# G826X.net
KiCad netlist of a schematic drawn in EAGLE
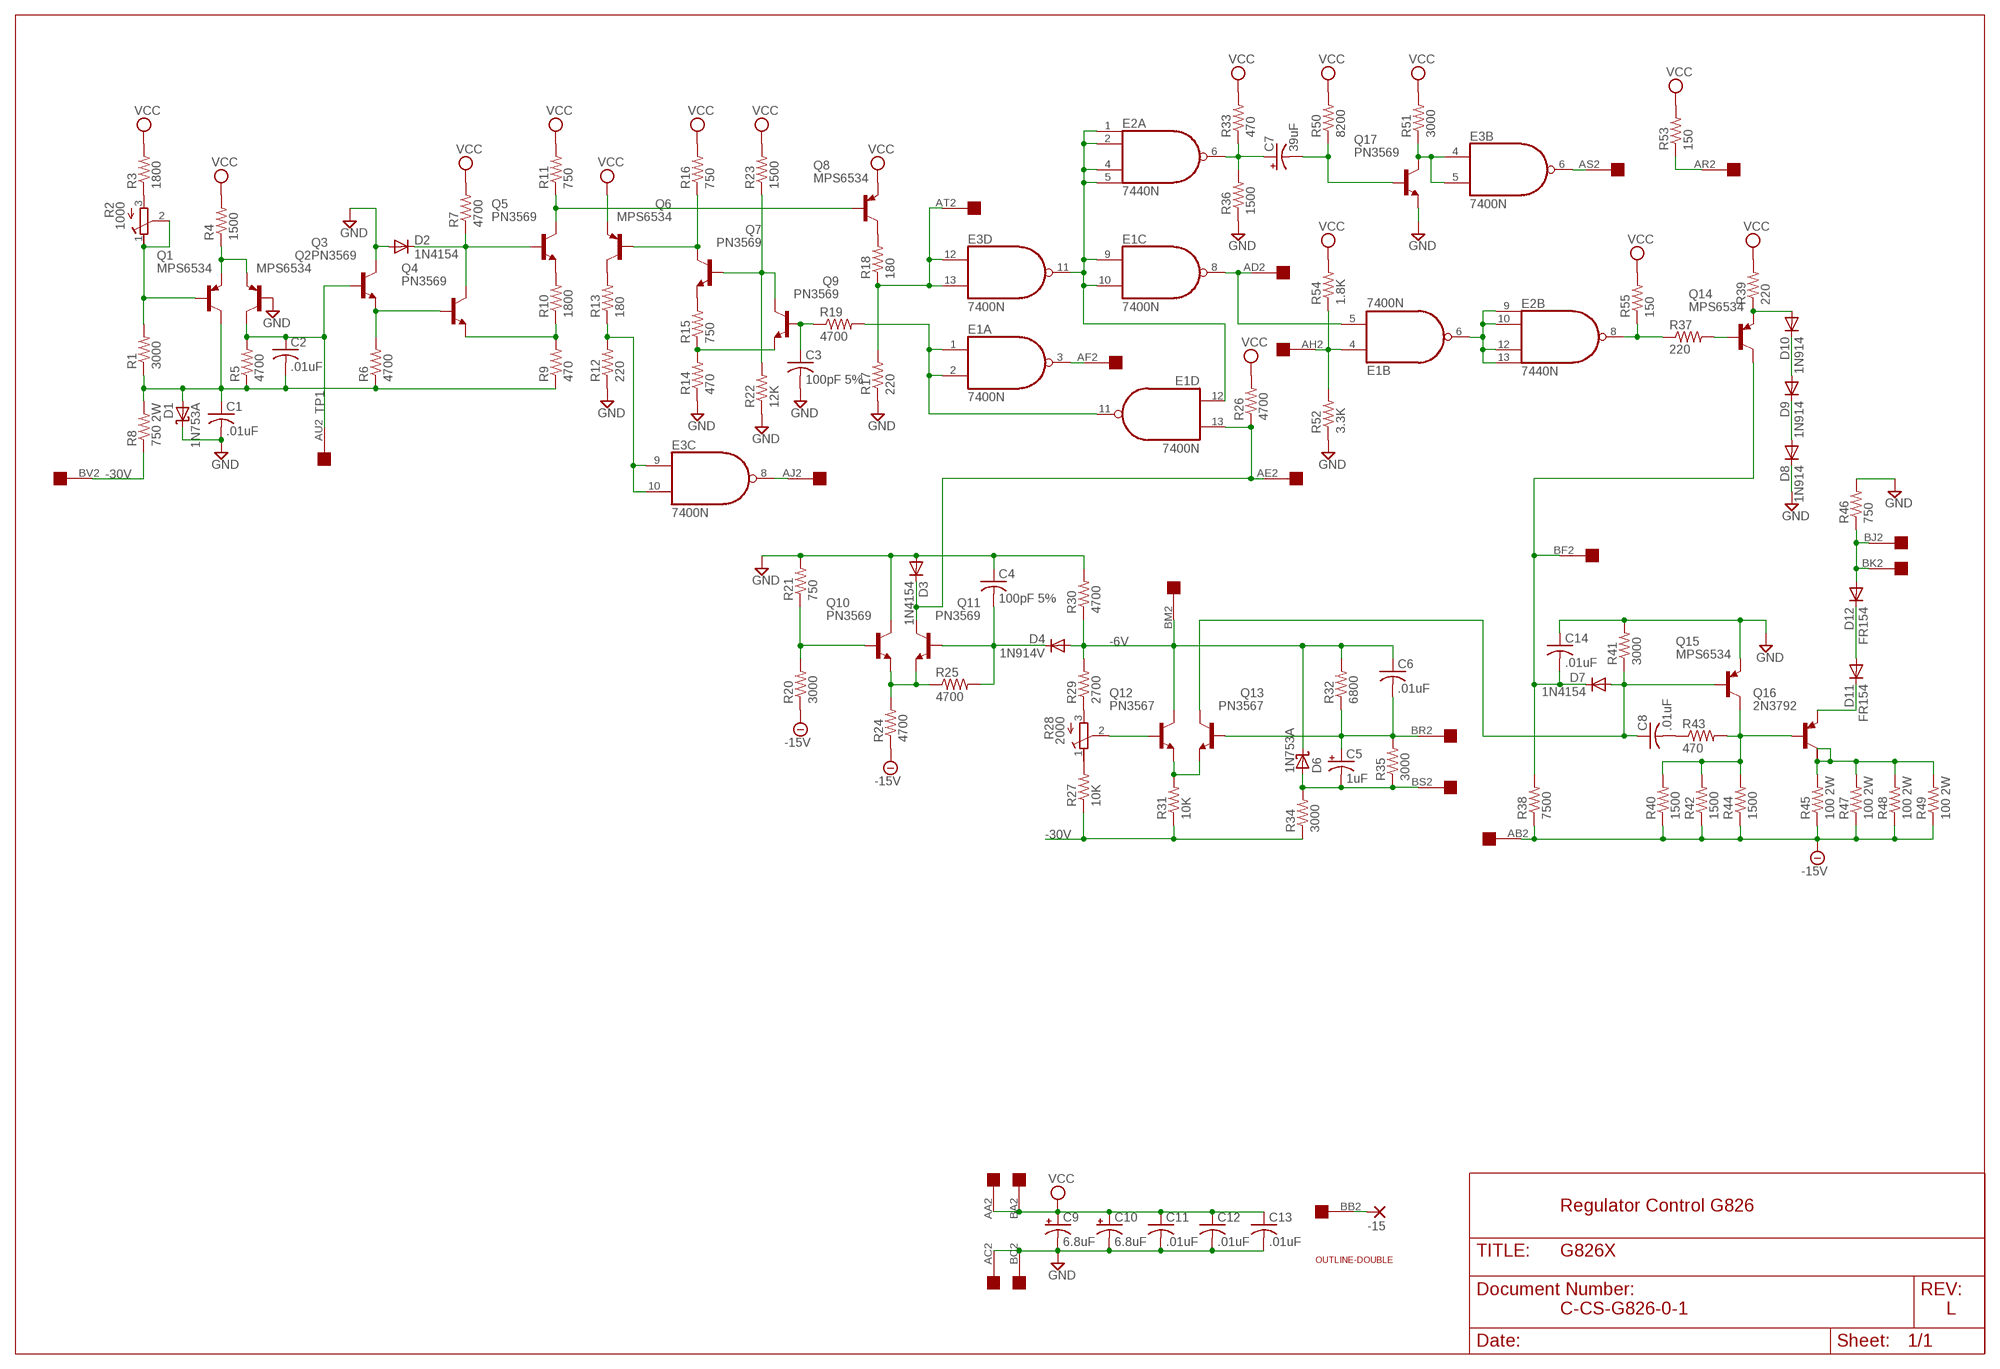
[diagram p0: schematic, sheet 1]

(export (version "E")
  (design (tool "Eeschema 10.0.6"))
  (components
    (comp (ref "-15")
      (value "1,6/0,8")
      (footprint "eagle-import:1,6_0,8")
      (libsource (lib "eagle-import") (part "1,6/0,8"))
    )
    (comp (ref "C1")
      (value ".01uF")
      (footprint "eagle-import:C050-025X075")
      (libsource (lib "eagle-import") (part "C-US050-025X075"))
    )
    (comp (ref "C2")
      (value ".01uF")
      (footprint "eagle-import:C050-025X075")
      (libsource (lib "eagle-import") (part "C-US050-025X075"))
    )
    (comp (ref "C3")
      (value "100pF 5%")
      (footprint "eagle-import:C050-025X075")
      (libsource (lib "eagle-import") (part "C-US050-025X075"))
    )
    (comp (ref "C4")
      (value "100pF 5%")
      (footprint "eagle-import:C050-025X075")
      (libsource (lib "eagle-import") (part "C-US050-025X075"))
    )
    (comp (ref "C5")
      (value "1uF")
      (footprint "eagle-import:E15-5")
      (libsource (lib "eagle-import") (part "CPOL-USE15-5AXIAL"))
    )
    (comp (ref "C6")
      (value ".01uF")
      (footprint "eagle-import:C050-025X075")
      (libsource (lib "eagle-import") (part "C-US050-025X075"))
    )
    (comp (ref "C7")
      (value "39uF")
      (footprint "eagle-import:E22-6")
      (libsource (lib "eagle-import") (part "CPOL-USE22-6AXIAL"))
    )
    (comp (ref "C8")
      (value ".01uF")
      (footprint "eagle-import:C050-025X075")
      (libsource (lib "eagle-import") (part "C-US050-025X075"))
    )
    (comp (ref "C9")
      (value "6.8uF")
      (footprint "eagle-import:E12-8")
      (libsource (lib "eagle-import") (part "CPOL-USE20-8AXIAL"))
    )
    (comp (ref "C10")
      (value "6.8uF")
      (footprint "eagle-import:E12-8")
      (libsource (lib "eagle-import") (part "CPOL-USE20-8AXIAL"))
    )
    (comp (ref "C11")
      (value ".01uF")
      (footprint "eagle-import:C050-025X075")
      (libsource (lib "eagle-import") (part "C-US050-025X075"))
    )
    (comp (ref "C12")
      (value ".01uF")
      (footprint "eagle-import:C050-025X075")
      (libsource (lib "eagle-import") (part "C-US050-025X075"))
    )
    (comp (ref "C13")
      (value ".01uF")
      (footprint "eagle-import:C050-025X075")
      (libsource (lib "eagle-import") (part "C-US050-025X075"))
    )
    (comp (ref "C14")
      (value ".01uF")
      (footprint "eagle-import:C050-025X075")
      (libsource (lib "eagle-import") (part "C-US050-025X075"))
    )
    (comp (ref "D1")
      (value "1N753A")
      (footprint "eagle-import:DO35-10")
      (libsource (lib "eagle-import") (part "BAT42"))
    )
    (comp (ref "D2")
      (value "1N4154")
      (footprint "eagle-import:DO35-10")
      (libsource (lib "eagle-import") (part "1N4148"))
    )
    (comp (ref "D3")
      (value "1N4154")
      (footprint "eagle-import:DO35-10")
      (libsource (lib "eagle-import") (part "1N4148"))
    )
    (comp (ref "D4")
      (value "1N914V")
      (footprint "eagle-import:DO35-10")
      (libsource (lib "eagle-import") (part "1N4148"))
    )
    (comp (ref "D6")
      (value "1N753A")
      (footprint "eagle-import:DO35-10")
      (libsource (lib "eagle-import") (part "BAT42"))
    )
    (comp (ref "D7")
      (value "1N4154")
      (footprint "eagle-import:DO35-10")
      (libsource (lib "eagle-import") (part "1N4148"))
    )
    (comp (ref "D8")
      (value "1N914")
      (footprint "eagle-import:DO35-10")
      (libsource (lib "eagle-import") (part "1N4148"))
    )
    (comp (ref "D9")
      (value "1N914")
      (footprint "eagle-import:DO35-10")
      (libsource (lib "eagle-import") (part "1N4148"))
    )
    (comp (ref "D10")
      (value "1N914")
      (footprint "eagle-import:DO35-10")
      (libsource (lib "eagle-import") (part "1N4148"))
    )
    (comp (ref "D11")
      (value "FR154")
      (footprint "eagle-import:DO41-10")
      (libsource (lib "eagle-import") (part "1N4004"))
    )
    (comp (ref "D12")
      (value "FR154")
      (footprint "eagle-import:DO41-10")
      (libsource (lib "eagle-import") (part "1N4004"))
    )
    (comp (ref "E1")
      (value "7400N")
      (footprint "eagle-import:DIL14")
      (libsource (lib "eagle-import") (part "7400N"))
    )
    (comp (ref "E2")
      (value "7440N")
      (footprint "eagle-import:DIL14")
      (libsource (lib "eagle-import") (part "7420NS"))
    )
    (comp (ref "E3")
      (value "7400N")
      (footprint "eagle-import:DIL14")
      (libsource (lib "eagle-import") (part "7400N"))
    )
    (comp (ref "Q1")
      (value "MPS6534")
      (footprint "eagle-import:TO39")
      (libsource (lib "eagle-import") (part "2N2904"))
    )
    (comp (ref "Q2")
      (value "MPS6534")
      (footprint "eagle-import:TO39")
      (libsource (lib "eagle-import") (part "2N2904"))
    )
    (comp (ref "Q3")
      (value "PN3569")
      (footprint "eagle-import:TO5")
      (libsource (lib "eagle-import") (part "2N2219"))
    )
    (comp (ref "Q4")
      (value "PN3569")
      (footprint "eagle-import:TO5")
      (libsource (lib "eagle-import") (part "2N2219"))
    )
    (comp (ref "Q5")
      (value "PN3569")
      (footprint "eagle-import:TO5")
      (libsource (lib "eagle-import") (part "2N2219"))
    )
    (comp (ref "Q6")
      (value "MPS6534")
      (footprint "eagle-import:TO39")
      (libsource (lib "eagle-import") (part "2N2904"))
    )
    (comp (ref "Q7")
      (value "PN3569")
      (footprint "eagle-import:TO5")
      (libsource (lib "eagle-import") (part "2N2219"))
    )
    (comp (ref "Q8")
      (value "MPS6534")
      (footprint "eagle-import:TO39")
      (libsource (lib "eagle-import") (part "2N2904"))
    )
    (comp (ref "Q9")
      (value "PN3569")
      (footprint "eagle-import:TO5")
      (libsource (lib "eagle-import") (part "2N2219"))
    )
    (comp (ref "Q10")
      (value "PN3569")
      (footprint "eagle-import:TO5")
      (libsource (lib "eagle-import") (part "2N2219"))
    )
    (comp (ref "Q11")
      (value "PN3569")
      (footprint "eagle-import:TO5")
      (libsource (lib "eagle-import") (part "2N2219"))
    )
    (comp (ref "Q12")
      (value "PN3567")
      (footprint "eagle-import:TO5")
      (libsource (lib "eagle-import") (part "2N2219"))
    )
    (comp (ref "Q13")
      (value "PN3567")
      (footprint "eagle-import:TO5")
      (libsource (lib "eagle-import") (part "2N2219"))
    )
    (comp (ref "Q14")
      (value "MPS6534")
      (footprint "eagle-import:TO39")
      (libsource (lib "eagle-import") (part "2N2904"))
    )
    (comp (ref "Q15")
      (value "MPS6534")
      (footprint "eagle-import:TO39")
      (libsource (lib "eagle-import") (part "2N2904"))
    )
    (comp (ref "Q16")
      (value "2N3792")
      (footprint "eagle-import:TO3")
      (libsource (lib "eagle-import") (part "2N4902"))
    )
    (comp (ref "Q17")
      (value "PN3569")
      (footprint "eagle-import:TO5")
      (libsource (lib "eagle-import") (part "2N2219"))
    )
    (comp (ref "R1")
      (value "3000")
      (footprint "eagle-import:0207_10")
      (libsource (lib "eagle-import") (part "R-US_0207/10"))
    )
    (comp (ref "R2")
      (value "1000")
      (footprint "eagle-import:3006Y")
      (libsource (lib "eagle-import") (part "275P"))
    )
    (comp (ref "R3")
      (value "1800")
      (footprint "eagle-import:0207_10")
      (libsource (lib "eagle-import") (part "R-US_0207/10"))
    )
    (comp (ref "R4")
      (value "1500")
      (footprint "eagle-import:0207_10")
      (libsource (lib "eagle-import") (part "R-US_0207/10"))
    )
    (comp (ref "R5")
      (value "4700")
      (footprint "eagle-import:0207_10")
      (libsource (lib "eagle-import") (part "R-US_0207/10"))
    )
    (comp (ref "R6")
      (value "4700")
      (footprint "eagle-import:0207_10")
      (libsource (lib "eagle-import") (part "R-US_0207/10"))
    )
    (comp (ref "R7")
      (value "4700")
      (footprint "eagle-import:0207_10")
      (libsource (lib "eagle-import") (part "R-US_0207/10"))
    )
    (comp (ref "R8")
      (value "750 2W")
      (footprint "eagle-import:0818_25")
      (libsource (lib "eagle-import") (part "R-US_0818/25"))
    )
    (comp (ref "R9")
      (value "470")
      (footprint "eagle-import:0207_10")
      (libsource (lib "eagle-import") (part "R-US_0207/10"))
    )
    (comp (ref "R10")
      (value "1800")
      (footprint "eagle-import:0207_10")
      (libsource (lib "eagle-import") (part "R-US_0207/10"))
    )
    (comp (ref "R11")
      (value "750")
      (footprint "eagle-import:0207_10")
      (libsource (lib "eagle-import") (part "R-US_0207/10"))
    )
    (comp (ref "R12")
      (value "220")
      (footprint "eagle-import:0207_10")
      (libsource (lib "eagle-import") (part "R-US_0207/10"))
    )
    (comp (ref "R13")
      (value "180")
      (footprint "eagle-import:0207_10")
      (libsource (lib "eagle-import") (part "R-US_0207/10"))
    )
    (comp (ref "R14")
      (value "470")
      (footprint "eagle-import:0207_10")
      (libsource (lib "eagle-import") (part "R-US_0207/10"))
    )
    (comp (ref "R15")
      (value "750")
      (footprint "eagle-import:0207_10")
      (libsource (lib "eagle-import") (part "R-US_0207/10"))
    )
    (comp (ref "R16")
      (value "750")
      (footprint "eagle-import:0207_10")
      (libsource (lib "eagle-import") (part "R-US_0207/10"))
    )
    (comp (ref "R17")
      (value "220")
      (footprint "eagle-import:0207_10")
      (libsource (lib "eagle-import") (part "R-US_0207/10"))
    )
    (comp (ref "R18")
      (value "180")
      (footprint "eagle-import:0207_10")
      (libsource (lib "eagle-import") (part "R-US_0207/10"))
    )
    (comp (ref "R19")
      (value "4700")
      (footprint "eagle-import:0207_10")
      (libsource (lib "eagle-import") (part "R-US_0207/10"))
    )
    (comp (ref "R20")
      (value "3000")
      (footprint "eagle-import:0207_10")
      (libsource (lib "eagle-import") (part "R-US_0207/10"))
    )
    (comp (ref "R21")
      (value "750")
      (footprint "eagle-import:0207_10")
      (libsource (lib "eagle-import") (part "R-US_0207/10"))
    )
    (comp (ref "R22")
      (value "12K")
      (footprint "eagle-import:0207_10")
      (libsource (lib "eagle-import") (part "R-US_0207/10"))
    )
    (comp (ref "R23")
      (value "1500")
      (footprint "eagle-import:0207_10")
      (libsource (lib "eagle-import") (part "R-US_0207/10"))
    )
    (comp (ref "R24")
      (value "4700")
      (footprint "eagle-import:0207_10")
      (libsource (lib "eagle-import") (part "R-US_0207/10"))
    )
    (comp (ref "R25")
      (value "4700")
      (footprint "eagle-import:0207_10")
      (libsource (lib "eagle-import") (part "R-US_0207/10"))
    )
    (comp (ref "R26")
      (value "4700")
      (footprint "eagle-import:0207_10")
      (libsource (lib "eagle-import") (part "R-US_0207/10"))
    )
    (comp (ref "R27")
      (value "10K")
      (footprint "eagle-import:0207_10")
      (libsource (lib "eagle-import") (part "R-US_0207/10"))
    )
    (comp (ref "R28")
      (value "2000")
      (footprint "eagle-import:3006Y")
      (libsource (lib "eagle-import") (part "275P"))
    )
    (comp (ref "R29")
      (value "2700")
      (footprint "eagle-import:0207_10")
      (libsource (lib "eagle-import") (part "R-US_0207/10"))
    )
    (comp (ref "R30")
      (value "4700")
      (footprint "eagle-import:0207_10")
      (libsource (lib "eagle-import") (part "R-US_0207/10"))
    )
    (comp (ref "R31")
      (value "10K")
      (footprint "eagle-import:0207_10")
      (libsource (lib "eagle-import") (part "R-US_0207/10"))
    )
    (comp (ref "R32")
      (value "6800")
      (footprint "eagle-import:0207_10")
      (libsource (lib "eagle-import") (part "R-US_0207/10"))
    )
    (comp (ref "R33")
      (value "470")
      (footprint "eagle-import:0207_10")
      (libsource (lib "eagle-import") (part "R-US_0207/10"))
    )
    (comp (ref "R34")
      (value "3000")
      (footprint "eagle-import:0207_10")
      (libsource (lib "eagle-import") (part "R-US_0207/10"))
    )
    (comp (ref "R35")
      (value "3000")
      (footprint "eagle-import:0207_10")
      (libsource (lib "eagle-import") (part "R-US_0207/10"))
    )
    (comp (ref "R36")
      (value "1500")
      (footprint "eagle-import:0207_10")
      (libsource (lib "eagle-import") (part "R-US_0207/10"))
    )
    (comp (ref "R37")
      (value "220")
      (footprint "eagle-import:0207_10")
      (libsource (lib "eagle-import") (part "R-US_0207/10"))
    )
    (comp (ref "R38")
      (value "7500")
      (footprint "eagle-import:0207_10")
      (libsource (lib "eagle-import") (part "R-US_0207/10"))
    )
    (comp (ref "R39")
      (value "220")
      (footprint "eagle-import:0207_10")
      (libsource (lib "eagle-import") (part "R-US_0207/10"))
    )
    (comp (ref "R40")
      (value "1500")
      (footprint "eagle-import:0207_10")
      (libsource (lib "eagle-import") (part "R-US_0207/10"))
    )
    (comp (ref "R41")
      (value "3000")
      (footprint "eagle-import:0207_10")
      (libsource (lib "eagle-import") (part "R-US_0207/10"))
    )
    (comp (ref "R42")
      (value "1500")
      (footprint "eagle-import:0207_10")
      (libsource (lib "eagle-import") (part "R-US_0207/10"))
    )
    (comp (ref "R43")
      (value "470")
      (footprint "eagle-import:0207_10")
      (libsource (lib "eagle-import") (part "R-US_0207/10"))
    )
    (comp (ref "R44")
      (value "1500")
      (footprint "eagle-import:0207_10")
      (libsource (lib "eagle-import") (part "R-US_0207/10"))
    )
    (comp (ref "R45")
      (value "100 2W")
      (footprint "eagle-import:0818_25")
      (libsource (lib "eagle-import") (part "R-US_0818/25"))
    )
    (comp (ref "R46")
      (value "750")
      (footprint "eagle-import:0207_10")
      (libsource (lib "eagle-import") (part "R-US_0207/10"))
    )
    (comp (ref "R47")
      (value "100 2W")
      (footprint "eagle-import:0818_25")
      (libsource (lib "eagle-import") (part "R-US_0818/25"))
    )
    (comp (ref "R48")
      (value "100 2W")
      (footprint "eagle-import:0818_25")
      (libsource (lib "eagle-import") (part "R-US_0818/25"))
    )
    (comp (ref "R49")
      (value "100 2W")
      (footprint "eagle-import:0818_25")
      (libsource (lib "eagle-import") (part "R-US_0818/25"))
    )
    (comp (ref "R50")
      (value "8200")
      (footprint "eagle-import:0207_10")
      (libsource (lib "eagle-import") (part "R-US_0207/10"))
    )
    (comp (ref "R51")
      (value "3000")
      (footprint "eagle-import:0207_10")
      (libsource (lib "eagle-import") (part "R-US_0207/10"))
    )
    (comp (ref "R52")
      (value "3.3K")
      (footprint "eagle-import:0207_10")
      (libsource (lib "eagle-import") (part "R-US_0207/10"))
    )
    (comp (ref "R53")
      (value "150")
      (footprint "eagle-import:0207_10")
      (libsource (lib "eagle-import") (part "R-US_0207/10"))
    )
    (comp (ref "R54")
      (value "1.8K")
      (footprint "eagle-import:0207_10")
      (libsource (lib "eagle-import") (part "R-US_0207/10"))
    )
    (comp (ref "R55")
      (value "150")
      (footprint "eagle-import:0207_10")
      (libsource (lib "eagle-import") (part "R-US_0207/10"))
    )
    (comp (ref "U$1")
      (value "DOUBLE")
      (footprint "eagle-import:EDGE-CON4")
      (libsource (lib "eagle-import") (part "DOUBLE"))
    )
    (comp (ref "U$2")
      (value "OUTLINE-DOUBLE")
      (footprint "eagle-import:DOUBLE")
      (libsource (lib "eagle-import") (part "OUTLINE-DOUBLE"))
    )
  )
  (nets
    (net (code "1") (name "-15V") (class "Default")
      (node (ref "R20") (pin "1") (pinfunction "1_1") (pintype "passive"))
      (node (ref "R24") (pin "1") (pinfunction "1_1") (pintype "passive"))
      (node (ref "R38") (pin "1") (pinfunction "1_1") (pintype "passive"))
      (node (ref "R40") (pin "1") (pinfunction "1_1") (pintype "passive"))
      (node (ref "R42") (pin "1") (pinfunction "1_1") (pintype "passive"))
      (node (ref "R44") (pin "1") (pinfunction "1_1") (pintype "passive"))
      (node (ref "R45") (pin "1") (pinfunction "1_1") (pintype "passive"))
      (node (ref "R47") (pin "1") (pinfunction "1_1") (pintype "passive"))
      (node (ref "R48") (pin "1") (pinfunction "1_1") (pintype "passive"))
      (node (ref "R49") (pin "1") (pinfunction "1_1") (pintype "passive"))
      (node (ref "U$1") (pin "AB2") (pinfunction "1_AB2") (pintype "bidirectional"))
    )
    (net (code "2") (name "/-6V") (class "Default")
      (node (ref "C6") (pin "1") (pinfunction "1_1") (pintype "passive"))
      (node (ref "D4") (pin "A") (pinfunction "A_A") (pintype "passive"))
      (node (ref "D6") (pin "C") (pinfunction "C_C") (pintype "passive"))
      (node (ref "Q12") (pin "3") (pinfunction "C_3") (pintype "passive"))
      (node (ref "R29") (pin "2") (pinfunction "2_2") (pintype "passive"))
      (node (ref "R30") (pin "1") (pinfunction "1_1") (pintype "passive"))
      (node (ref "R32") (pin "2") (pinfunction "2_2") (pintype "passive"))
      (node (ref "U$1") (pin "BM2") (pinfunction "1_BM2") (pintype "bidirectional"))
    )
    (net (code "3") (name "/-30V") (class "Default")
      (node (ref "R27") (pin "1") (pinfunction "1_1") (pintype "passive"))
      (node (ref "R31") (pin "1") (pinfunction "1_1") (pintype "passive"))
      (node (ref "R34") (pin "1") (pinfunction "1_1") (pintype "passive"))
      (node (ref "R8") (pin "1") (pinfunction "1_1") (pintype "passive"))
      (node (ref "U$1") (pin "BV2") (pinfunction "1_BV2") (pintype "bidirectional"))
    )
    (net (code "4") (name "/TP1") (class "Default")
      (node (ref "C2") (pin "1") (pinfunction "1_1") (pintype "passive"))
      (node (ref "Q2") (pin "3") (pinfunction "C_3") (pintype "passive"))
      (node (ref "Q3") (pin "2") (pinfunction "B_2") (pintype "passive"))
      (node (ref "R5") (pin "2") (pinfunction "2_2") (pintype "passive"))
      (node (ref "U$1") (pin "AU2") (pinfunction "1_AU2") (pintype "bidirectional"))
    )
    (net (code "5") (name "GND") (class "Default")
      (node (ref "C1") (pin "2") (pinfunction "2_2") (pintype "passive"))
      (node (ref "C10") (pin "-") (pinfunction "-_-") (pintype "passive"))
      (node (ref "C11") (pin "2") (pinfunction "2_2") (pintype "passive"))
      (node (ref "C12") (pin "2") (pinfunction "2_2") (pintype "passive"))
      (node (ref "C13") (pin "2") (pinfunction "2_2") (pintype "passive"))
      (node (ref "C14") (pin "1") (pinfunction "1_1") (pintype "passive"))
      (node (ref "C3") (pin "2") (pinfunction "2_2") (pintype "passive"))
      (node (ref "C4") (pin "1") (pinfunction "1_1") (pintype "passive"))
      (node (ref "C9") (pin "-") (pinfunction "-_-") (pintype "passive"))
      (node (ref "D1") (pin "C") (pinfunction "C_C") (pintype "passive"))
      (node (ref "D2") (pin "A") (pinfunction "A_A") (pintype "passive"))
      (node (ref "D3") (pin "A") (pinfunction "A_A") (pintype "passive"))
      (node (ref "D8") (pin "C") (pinfunction "C_C") (pintype "passive"))
      (node (ref "Q10") (pin "3") (pinfunction "C_3") (pintype "passive"))
      (node (ref "Q15") (pin "1") (pinfunction "E_1") (pintype "passive"))
      (node (ref "Q17") (pin "1") (pinfunction "E_1") (pintype "passive"))
      (node (ref "Q2") (pin "2") (pinfunction "B_2") (pintype "passive"))
      (node (ref "Q3") (pin "3") (pinfunction "C_3") (pintype "passive"))
      (node (ref "R12") (pin "1") (pinfunction "1_1") (pintype "passive"))
      (node (ref "R14") (pin "1") (pinfunction "1_1") (pintype "passive"))
      (node (ref "R17") (pin "1") (pinfunction "1_1") (pintype "passive"))
      (node (ref "R21") (pin "2") (pinfunction "2_2") (pintype "passive"))
      (node (ref "R22") (pin "1") (pinfunction "1_1") (pintype "passive"))
      (node (ref "R30") (pin "2") (pinfunction "2_2") (pintype "passive"))
      (node (ref "R36") (pin "1") (pinfunction "1_1") (pintype "passive"))
      (node (ref "R41") (pin "2") (pinfunction "2_2") (pintype "passive"))
      (node (ref "R46") (pin "2") (pinfunction "2_2") (pintype "passive"))
      (node (ref "R52") (pin "1") (pinfunction "1_1") (pintype "passive"))
      (node (ref "U$1") (pin "AC2") (pinfunction "1_AC2") (pintype "bidirectional"))
      (node (ref "U$1") (pin "BC2") (pinfunction "1_BC2") (pintype "bidirectional"))
    )
    (net (code "6") (name "Net-(-15-P)") (class "Default")
      (node (ref "-15") (pin "1") (pinfunction "P_1") (pintype "passive"))
      (node (ref "U$1") (pin "BB2") (pinfunction "1_BB2") (pintype "bidirectional"))
    )
    (net (code "7") (name "Net-(C8-Pad2)") (class "Default")
      (node (ref "C8") (pin "2") (pinfunction "2_2") (pintype "passive"))
      (node (ref "R43") (pin "1") (pinfunction "1_1") (pintype "passive"))
    )
    (net (code "8") (name "Net-(D8-PadA)") (class "Default")
      (node (ref "D8") (pin "A") (pinfunction "A_A") (pintype "passive"))
      (node (ref "D9") (pin "C") (pinfunction "C_C") (pintype "passive"))
    )
    (net (code "9") (name "Net-(D10-PadC)") (class "Default")
      (node (ref "D10") (pin "C") (pinfunction "C_C") (pintype "passive"))
      (node (ref "D9") (pin "A") (pinfunction "A_A") (pintype "passive"))
    )
    (net (code "10") (name "Net-(D11-PadA)") (class "Default")
      (node (ref "D11") (pin "A") (pinfunction "A_A") (pintype "passive"))
      (node (ref "D12") (pin "C") (pinfunction "C_C") (pintype "passive"))
    )
    (net (code "11") (name "Net-(D11-PadC)") (class "Default")
      (node (ref "D11") (pin "C") (pinfunction "C_C") (pintype "passive"))
      (node (ref "Q16") (pin "E") (pinfunction "E_E") (pintype "passive"))
    )
    (net (code "12") (name "Net-(E1A-I0)") (class "Default")
      (node (ref "E1") (pin "1") (pinfunction "I0_1") (pintype "input"))
      (node (ref "E1") (pin "11") (pinfunction "O_11") (pintype "output"))
      (node (ref "E1") (pin "2") (pinfunction "I1_2") (pintype "input"))
      (node (ref "R19") (pin "2") (pinfunction "2_2") (pintype "passive"))
    )
    (net (code "13") (name "Net-(E1A-O)") (class "Default")
      (node (ref "E1") (pin "3") (pinfunction "O_3") (pintype "output"))
      (node (ref "U$1") (pin "AF2") (pinfunction "1_AF2") (pintype "bidirectional"))
    )
    (net (code "14") (name "Net-(E1B-I0)") (class "Default")
      (node (ref "E1") (pin "4") (pinfunction "I0_4") (pintype "input"))
      (node (ref "R52") (pin "2") (pinfunction "2_2") (pintype "passive"))
      (node (ref "R54") (pin "1") (pinfunction "1_1") (pintype "passive"))
      (node (ref "U$1") (pin "AH2") (pinfunction "1_AH2") (pintype "bidirectional"))
    )
    (net (code "15") (name "Net-(E1B-I1)") (class "Default")
      (node (ref "E1") (pin "5") (pinfunction "I1_5") (pintype "input"))
      (node (ref "E1") (pin "8") (pinfunction "O_8") (pintype "output"))
      (node (ref "U$1") (pin "AD2") (pinfunction "1_AD2") (pintype "bidirectional"))
    )
    (net (code "16") (name "Net-(E1B-O)") (class "Default")
      (node (ref "E1") (pin "6") (pinfunction "O_6") (pintype "output"))
      (node (ref "E2") (pin "10") (pinfunction "I1_10") (pintype "input"))
      (node (ref "E2") (pin "12") (pinfunction "I2_12") (pintype "input"))
      (node (ref "E2") (pin "13") (pinfunction "I3_13") (pintype "input"))
      (node (ref "E2") (pin "9") (pinfunction "I0_9") (pintype "input"))
    )
    (net (code "17") (name "Net-(E1C-I0)") (class "Default")
      (node (ref "E1") (pin "10") (pinfunction "I1_10") (pintype "input"))
      (node (ref "E1") (pin "12") (pinfunction "I0_12") (pintype "input"))
      (node (ref "E1") (pin "9") (pinfunction "I0_9") (pintype "input"))
      (node (ref "E2") (pin "1") (pinfunction "I0_1") (pintype "input"))
      (node (ref "E2") (pin "2") (pinfunction "I1_2") (pintype "input"))
      (node (ref "E2") (pin "4") (pinfunction "I2_4") (pintype "input"))
      (node (ref "E2") (pin "5") (pinfunction "I3_5") (pintype "input"))
      (node (ref "E3") (pin "11") (pinfunction "O_11") (pintype "output"))
    )
    (net (code "18") (name "Net-(E1D-I1)") (class "Default")
      (node (ref "D3") (pin "C") (pinfunction "C_C") (pintype "passive"))
      (node (ref "E1") (pin "13") (pinfunction "I1_13") (pintype "input"))
      (node (ref "Q11") (pin "3") (pinfunction "C_3") (pintype "passive"))
      (node (ref "R26") (pin "1") (pinfunction "1_1") (pintype "passive"))
      (node (ref "U$1") (pin "AE2") (pinfunction "1_AE2") (pintype "bidirectional"))
    )
    (net (code "19") (name "Net-(E2A-O)") (class "Default")
      (node (ref "C7") (pin "+") (pinfunction "+_+") (pintype "passive"))
      (node (ref "E2") (pin "6") (pinfunction "O_6") (pintype "output"))
      (node (ref "R33") (pin "1") (pinfunction "1_1") (pintype "passive"))
      (node (ref "R36") (pin "2") (pinfunction "2_2") (pintype "passive"))
    )
    (net (code "20") (name "Net-(E2B-O)") (class "Default")
      (node (ref "E2") (pin "8") (pinfunction "O_8") (pintype "output"))
      (node (ref "R37") (pin "1") (pinfunction "1_1") (pintype "passive"))
      (node (ref "R55") (pin "1") (pinfunction "1_1") (pintype "passive"))
    )
    (net (code "21") (name "Net-(E3B-I0)") (class "Default")
      (node (ref "E3") (pin "4") (pinfunction "I0_4") (pintype "input"))
      (node (ref "E3") (pin "5") (pinfunction "I1_5") (pintype "input"))
      (node (ref "Q17") (pin "3") (pinfunction "C_3") (pintype "passive"))
      (node (ref "R51") (pin "1") (pinfunction "1_1") (pintype "passive"))
    )
    (net (code "22") (name "Net-(E3B-O)") (class "Default")
      (node (ref "E3") (pin "6") (pinfunction "O_6") (pintype "output"))
      (node (ref "U$1") (pin "AS2") (pinfunction "1_AS2") (pintype "bidirectional"))
    )
    (net (code "23") (name "Net-(E3C-I0)") (class "Default")
      (node (ref "E3") (pin "10") (pinfunction "I1_10") (pintype "input"))
      (node (ref "E3") (pin "9") (pinfunction "I0_9") (pintype "input"))
      (node (ref "R12") (pin "2") (pinfunction "2_2") (pintype "passive"))
      (node (ref "R13") (pin "1") (pinfunction "1_1") (pintype "passive"))
    )
    (net (code "24") (name "Net-(E3C-O)") (class "Default")
      (node (ref "E3") (pin "8") (pinfunction "O_8") (pintype "output"))
      (node (ref "U$1") (pin "AJ2") (pinfunction "1_AJ2") (pintype "bidirectional"))
    )
    (net (code "25") (name "Net-(E3D-I0)") (class "Default")
      (node (ref "E3") (pin "12") (pinfunction "I0_12") (pintype "input"))
      (node (ref "E3") (pin "13") (pinfunction "I1_13") (pintype "input"))
      (node (ref "R17") (pin "2") (pinfunction "2_2") (pintype "passive"))
      (node (ref "R18") (pin "1") (pinfunction "1_1") (pintype "passive"))
      (node (ref "U$1") (pin "AT2") (pinfunction "1_AT2") (pintype "bidirectional"))
    )
    (net (code "26") (name "Net-(Q1-B)") (class "Default")
      (node (ref "Q1") (pin "2") (pinfunction "B_2") (pintype "passive"))
      (node (ref "R1") (pin "2") (pinfunction "2_2") (pintype "passive"))
      (node (ref "R2") (pin "1") (pinfunction "A_1") (pintype "passive"))
      (node (ref "R2") (pin "2") (pinfunction "S_2") (pintype "passive"))
    )
    (net (code "27") (name "Net-(Q1-C)") (class "Default")
      (node (ref "C1") (pin "1") (pinfunction "1_1") (pintype "passive"))
      (node (ref "C2") (pin "2") (pinfunction "2_2") (pintype "passive"))
      (node (ref "D1") (pin "A") (pinfunction "A_A") (pintype "passive"))
      (node (ref "Q1") (pin "3") (pinfunction "C_3") (pintype "passive"))
      (node (ref "R1") (pin "1") (pinfunction "1_1") (pintype "passive"))
      (node (ref "R5") (pin "1") (pinfunction "1_1") (pintype "passive"))
      (node (ref "R6") (pin "1") (pinfunction "1_1") (pintype "passive"))
      (node (ref "R8") (pin "2") (pinfunction "2_2") (pintype "passive"))
      (node (ref "R9") (pin "1") (pinfunction "1_1") (pintype "passive"))
    )
    (net (code "28") (name "Net-(Q1-E)") (class "Default")
      (node (ref "Q1") (pin "1") (pinfunction "E_1") (pintype "passive"))
      (node (ref "Q2") (pin "1") (pinfunction "E_1") (pintype "passive"))
      (node (ref "R4") (pin "1") (pinfunction "1_1") (pintype "passive"))
    )
    (net (code "29") (name "Net-(Q3-E)") (class "Default")
      (node (ref "Q3") (pin "1") (pinfunction "E_1") (pintype "passive"))
      (node (ref "Q4") (pin "2") (pinfunction "B_2") (pintype "passive"))
      (node (ref "R6") (pin "2") (pinfunction "2_2") (pintype "passive"))
    )
    (net (code "30") (name "Net-(Q4-C)") (class "Default")
      (node (ref "D2") (pin "C") (pinfunction "C_C") (pintype "passive"))
      (node (ref "Q4") (pin "3") (pinfunction "C_3") (pintype "passive"))
      (node (ref "Q5") (pin "2") (pinfunction "B_2") (pintype "passive"))
      (node (ref "R7") (pin "1") (pinfunction "1_1") (pintype "passive"))
    )
    (net (code "31") (name "Net-(Q4-E)") (class "Default")
      (node (ref "Q4") (pin "1") (pinfunction "E_1") (pintype "passive"))
      (node (ref "R10") (pin "1") (pinfunction "1_1") (pintype "passive"))
      (node (ref "R9") (pin "2") (pinfunction "2_2") (pintype "passive"))
    )
    (net (code "32") (name "Net-(Q5-C)") (class "Default")
      (node (ref "Q5") (pin "3") (pinfunction "C_3") (pintype "passive"))
      (node (ref "Q8") (pin "2") (pinfunction "B_2") (pintype "passive"))
      (node (ref "R11") (pin "1") (pinfunction "1_1") (pintype "passive"))
    )
    (net (code "33") (name "Net-(Q5-E)") (class "Default")
      (node (ref "Q5") (pin "1") (pinfunction "E_1") (pintype "passive"))
      (node (ref "R10") (pin "2") (pinfunction "2_2") (pintype "passive"))
    )
    (net (code "34") (name "Net-(Q6-B)") (class "Default")
      (node (ref "Q6") (pin "2") (pinfunction "B_2") (pintype "passive"))
      (node (ref "Q7") (pin "3") (pinfunction "C_3") (pintype "passive"))
      (node (ref "R16") (pin "1") (pinfunction "1_1") (pintype "passive"))
    )
    (net (code "35") (name "Net-(Q6-C)") (class "Default")
      (node (ref "Q6") (pin "3") (pinfunction "C_3") (pintype "passive"))
      (node (ref "R13") (pin "2") (pinfunction "2_2") (pintype "passive"))
    )
    (net (code "36") (name "Net-(Q7-B)") (class "Default")
      (node (ref "Q7") (pin "2") (pinfunction "B_2") (pintype "passive"))
      (node (ref "Q9") (pin "3") (pinfunction "C_3") (pintype "passive"))
      (node (ref "R22") (pin "2") (pinfunction "2_2") (pintype "passive"))
      (node (ref "R23") (pin "1") (pinfunction "1_1") (pintype "passive"))
    )
    (net (code "37") (name "Net-(Q7-E)") (class "Default")
      (node (ref "Q7") (pin "1") (pinfunction "E_1") (pintype "passive"))
      (node (ref "R15") (pin "2") (pinfunction "2_2") (pintype "passive"))
    )
    (net (code "38") (name "Net-(Q8-C)") (class "Default")
      (node (ref "Q8") (pin "3") (pinfunction "C_3") (pintype "passive"))
      (node (ref "R18") (pin "2") (pinfunction "2_2") (pintype "passive"))
    )
    (net (code "39") (name "Net-(Q9-B)") (class "Default")
      (node (ref "C3") (pin "1") (pinfunction "1_1") (pintype "passive"))
      (node (ref "Q9") (pin "2") (pinfunction "B_2") (pintype "passive"))
      (node (ref "R19") (pin "1") (pinfunction "1_1") (pintype "passive"))
    )
    (net (code "40") (name "Net-(Q9-E)") (class "Default")
      (node (ref "Q9") (pin "1") (pinfunction "E_1") (pintype "passive"))
      (node (ref "R14") (pin "2") (pinfunction "2_2") (pintype "passive"))
      (node (ref "R15") (pin "1") (pinfunction "1_1") (pintype "passive"))
    )
    (net (code "41") (name "Net-(Q10-B)") (class "Default")
      (node (ref "Q10") (pin "2") (pinfunction "B_2") (pintype "passive"))
      (node (ref "R20") (pin "2") (pinfunction "2_2") (pintype "passive"))
      (node (ref "R21") (pin "1") (pinfunction "1_1") (pintype "passive"))
    )
    (net (code "42") (name "Net-(Q10-E)") (class "Default")
      (node (ref "Q10") (pin "1") (pinfunction "E_1") (pintype "passive"))
      (node (ref "Q11") (pin "1") (pinfunction "E_1") (pintype "passive"))
      (node (ref "R24") (pin "2") (pinfunction "2_2") (pintype "passive"))
      (node (ref "R25") (pin "1") (pinfunction "1_1") (pintype "passive"))
    )
    (net (code "43") (name "Net-(Q11-B)") (class "Default")
      (node (ref "C4") (pin "2") (pinfunction "2_2") (pintype "passive"))
      (node (ref "D4") (pin "C") (pinfunction "C_C") (pintype "passive"))
      (node (ref "Q11") (pin "2") (pinfunction "B_2") (pintype "passive"))
      (node (ref "R25") (pin "2") (pinfunction "2_2") (pintype "passive"))
    )
    (net (code "44") (name "Net-(Q12-B)") (class "Default")
      (node (ref "Q12") (pin "2") (pinfunction "B_2") (pintype "passive"))
      (node (ref "R28") (pin "2") (pinfunction "S_2") (pintype "passive"))
    )
    (net (code "45") (name "Net-(Q12-E)") (class "Default")
      (node (ref "Q12") (pin "1") (pinfunction "E_1") (pintype "passive"))
      (node (ref "Q13") (pin "1") (pinfunction "E_1") (pintype "passive"))
      (node (ref "R31") (pin "2") (pinfunction "2_2") (pintype "passive"))
    )
    (net (code "46") (name "Net-(Q13-B)") (class "Default")
      (node (ref "C5") (pin "+") (pinfunction "+_+") (pintype "passive"))
      (node (ref "C6") (pin "2") (pinfunction "2_2") (pintype "passive"))
      (node (ref "Q13") (pin "2") (pinfunction "B_2") (pintype "passive"))
      (node (ref "R32") (pin "1") (pinfunction "1_1") (pintype "passive"))
      (node (ref "R35") (pin "2") (pinfunction "2_2") (pintype "passive"))
      (node (ref "U$1") (pin "BR2") (pinfunction "1_BR2") (pintype "bidirectional"))
    )
    (net (code "47") (name "Net-(Q13-C)") (class "Default")
      (node (ref "C8") (pin "1") (pinfunction "1_1") (pintype "passive"))
      (node (ref "D7") (pin "A") (pinfunction "A_A") (pintype "passive"))
      (node (ref "Q13") (pin "3") (pinfunction "C_3") (pintype "passive"))
      (node (ref "Q15") (pin "2") (pinfunction "B_2") (pintype "passive"))
      (node (ref "R41") (pin "1") (pinfunction "1_1") (pintype "passive"))
    )
    (net (code "48") (name "Net-(Q14-B)") (class "Default")
      (node (ref "Q14") (pin "2") (pinfunction "B_2") (pintype "passive"))
      (node (ref "R37") (pin "2") (pinfunction "2_2") (pintype "passive"))
    )
    (net (code "49") (name "Net-(Q14-C)") (class "Default")
      (node (ref "C14") (pin "2") (pinfunction "2_2") (pintype "passive"))
      (node (ref "D7") (pin "C") (pinfunction "C_C") (pintype "passive"))
      (node (ref "Q14") (pin "3") (pinfunction "C_3") (pintype "passive"))
      (node (ref "R38") (pin "2") (pinfunction "2_2") (pintype "passive"))
      (node (ref "U$1") (pin "BF2") (pinfunction "1_BF2") (pintype "bidirectional"))
    )
    (net (code "50") (name "Net-(Q14-E)") (class "Default")
      (node (ref "D10") (pin "A") (pinfunction "A_A") (pintype "passive"))
      (node (ref "Q14") (pin "1") (pinfunction "E_1") (pintype "passive"))
      (node (ref "R39") (pin "1") (pinfunction "1_1") (pintype "passive"))
    )
    (net (code "51") (name "Net-(Q15-C)") (class "Default")
      (node (ref "Q15") (pin "3") (pinfunction "C_3") (pintype "passive"))
      (node (ref "Q16") (pin "B") (pinfunction "B_B") (pintype "passive"))
      (node (ref "R40") (pin "2") (pinfunction "2_2") (pintype "passive"))
      (node (ref "R42") (pin "2") (pinfunction "2_2") (pintype "passive"))
      (node (ref "R43") (pin "2") (pinfunction "2_2") (pintype "passive"))
      (node (ref "R44") (pin "2") (pinfunction "2_2") (pintype "passive"))
    )
    (net (code "52") (name "Net-(Q16-PadC)") (class "Default")
      (node (ref "Q16") (pin "C") (pinfunction "C_C") (pintype "passive"))
      (node (ref "Q16") (pin "C/") (pinfunction "C/_C/") (pintype "passive"))
      (node (ref "R45") (pin "2") (pinfunction "2_2") (pintype "passive"))
      (node (ref "R47") (pin "2") (pinfunction "2_2") (pintype "passive"))
      (node (ref "R48") (pin "2") (pinfunction "2_2") (pintype "passive"))
      (node (ref "R49") (pin "2") (pinfunction "2_2") (pintype "passive"))
    )
    (net (code "53") (name "Net-(Q17-B)") (class "Default")
      (node (ref "C7") (pin "-") (pinfunction "-_-") (pintype "passive"))
      (node (ref "Q17") (pin "2") (pinfunction "B_2") (pintype "passive"))
      (node (ref "R50") (pin "1") (pinfunction "1_1") (pintype "passive"))
    )
    (net (code "54") (name "Net-(R2-E)") (class "Default")
      (node (ref "R2") (pin "3") (pinfunction "E_3") (pintype "passive"))
      (node (ref "R3") (pin "1") (pinfunction "1_1") (pintype "passive"))
    )
    (net (code "55") (name "Net-(R28-A)") (class "Default")
      (node (ref "R27") (pin "2") (pinfunction "2_2") (pintype "passive"))
      (node (ref "R28") (pin "1") (pinfunction "A_1") (pintype "passive"))
    )
    (net (code "56") (name "Net-(R28-E)") (class "Default")
      (node (ref "R28") (pin "3") (pinfunction "E_3") (pintype "passive"))
      (node (ref "R29") (pin "1") (pinfunction "1_1") (pintype "passive"))
    )
    (net (code "57") (name "Net-(U$1AB-1)") (class "Default")
      (node (ref "R53") (pin "1") (pinfunction "1_1") (pintype "passive"))
      (node (ref "U$1") (pin "AR2") (pinfunction "1_AR2") (pintype "bidirectional"))
    )
    (net (code "58") (name "Net-(U$1AZ-1)") (class "Default")
      (node (ref "D12") (pin "A") (pinfunction "A_A") (pintype "passive"))
      (node (ref "R46") (pin "1") (pinfunction "1_1") (pintype "passive"))
      (node (ref "U$1") (pin "BJ2") (pinfunction "1_BJ2") (pintype "bidirectional"))
      (node (ref "U$1") (pin "BK2") (pinfunction "1_BK2") (pintype "bidirectional"))
    )
    (net (code "59") (name "Net-(U$1BN-1)") (class "Default")
      (node (ref "C5") (pin "-") (pinfunction "-_-") (pintype "passive"))
      (node (ref "D6") (pin "A") (pinfunction "A_A") (pintype "passive"))
      (node (ref "R34") (pin "2") (pinfunction "2_2") (pintype "passive"))
      (node (ref "R35") (pin "1") (pinfunction "1_1") (pintype "passive"))
      (node (ref "U$1") (pin "BS2") (pinfunction "1_BS2") (pintype "bidirectional"))
    )
    (net (code "60") (name "VCC") (class "Default")
      (node (ref "C10") (pin "+") (pinfunction "+_+") (pintype "passive"))
      (node (ref "C11") (pin "1") (pinfunction "1_1") (pintype "passive"))
      (node (ref "C12") (pin "1") (pinfunction "1_1") (pintype "passive"))
      (node (ref "C13") (pin "1") (pinfunction "1_1") (pintype "passive"))
      (node (ref "C9") (pin "+") (pinfunction "+_+") (pintype "passive"))
      (node (ref "Q6") (pin "1") (pinfunction "E_1") (pintype "passive"))
      (node (ref "Q8") (pin "1") (pinfunction "E_1") (pintype "passive"))
      (node (ref "R11") (pin "2") (pinfunction "2_2") (pintype "passive"))
      (node (ref "R16") (pin "2") (pinfunction "2_2") (pintype "passive"))
      (node (ref "R23") (pin "2") (pinfunction "2_2") (pintype "passive"))
      (node (ref "R26") (pin "2") (pinfunction "2_2") (pintype "passive"))
      (node (ref "R3") (pin "2") (pinfunction "2_2") (pintype "passive"))
      (node (ref "R33") (pin "2") (pinfunction "2_2") (pintype "passive"))
      (node (ref "R39") (pin "2") (pinfunction "2_2") (pintype "passive"))
      (node (ref "R4") (pin "2") (pinfunction "2_2") (pintype "passive"))
      (node (ref "R50") (pin "2") (pinfunction "2_2") (pintype "passive"))
      (node (ref "R51") (pin "2") (pinfunction "2_2") (pintype "passive"))
      (node (ref "R53") (pin "2") (pinfunction "2_2") (pintype "passive"))
      (node (ref "R54") (pin "2") (pinfunction "2_2") (pintype "passive"))
      (node (ref "R55") (pin "2") (pinfunction "2_2") (pintype "passive"))
      (node (ref "R7") (pin "2") (pinfunction "2_2") (pintype "passive"))
      (node (ref "U$1") (pin "AA2") (pinfunction "1_AA2") (pintype "bidirectional"))
      (node (ref "U$1") (pin "BA2") (pinfunction "1_BA2") (pintype "bidirectional"))
    )
  )
)
